# design.net
KiCad netlist of a schematic drawn in EasyEDA
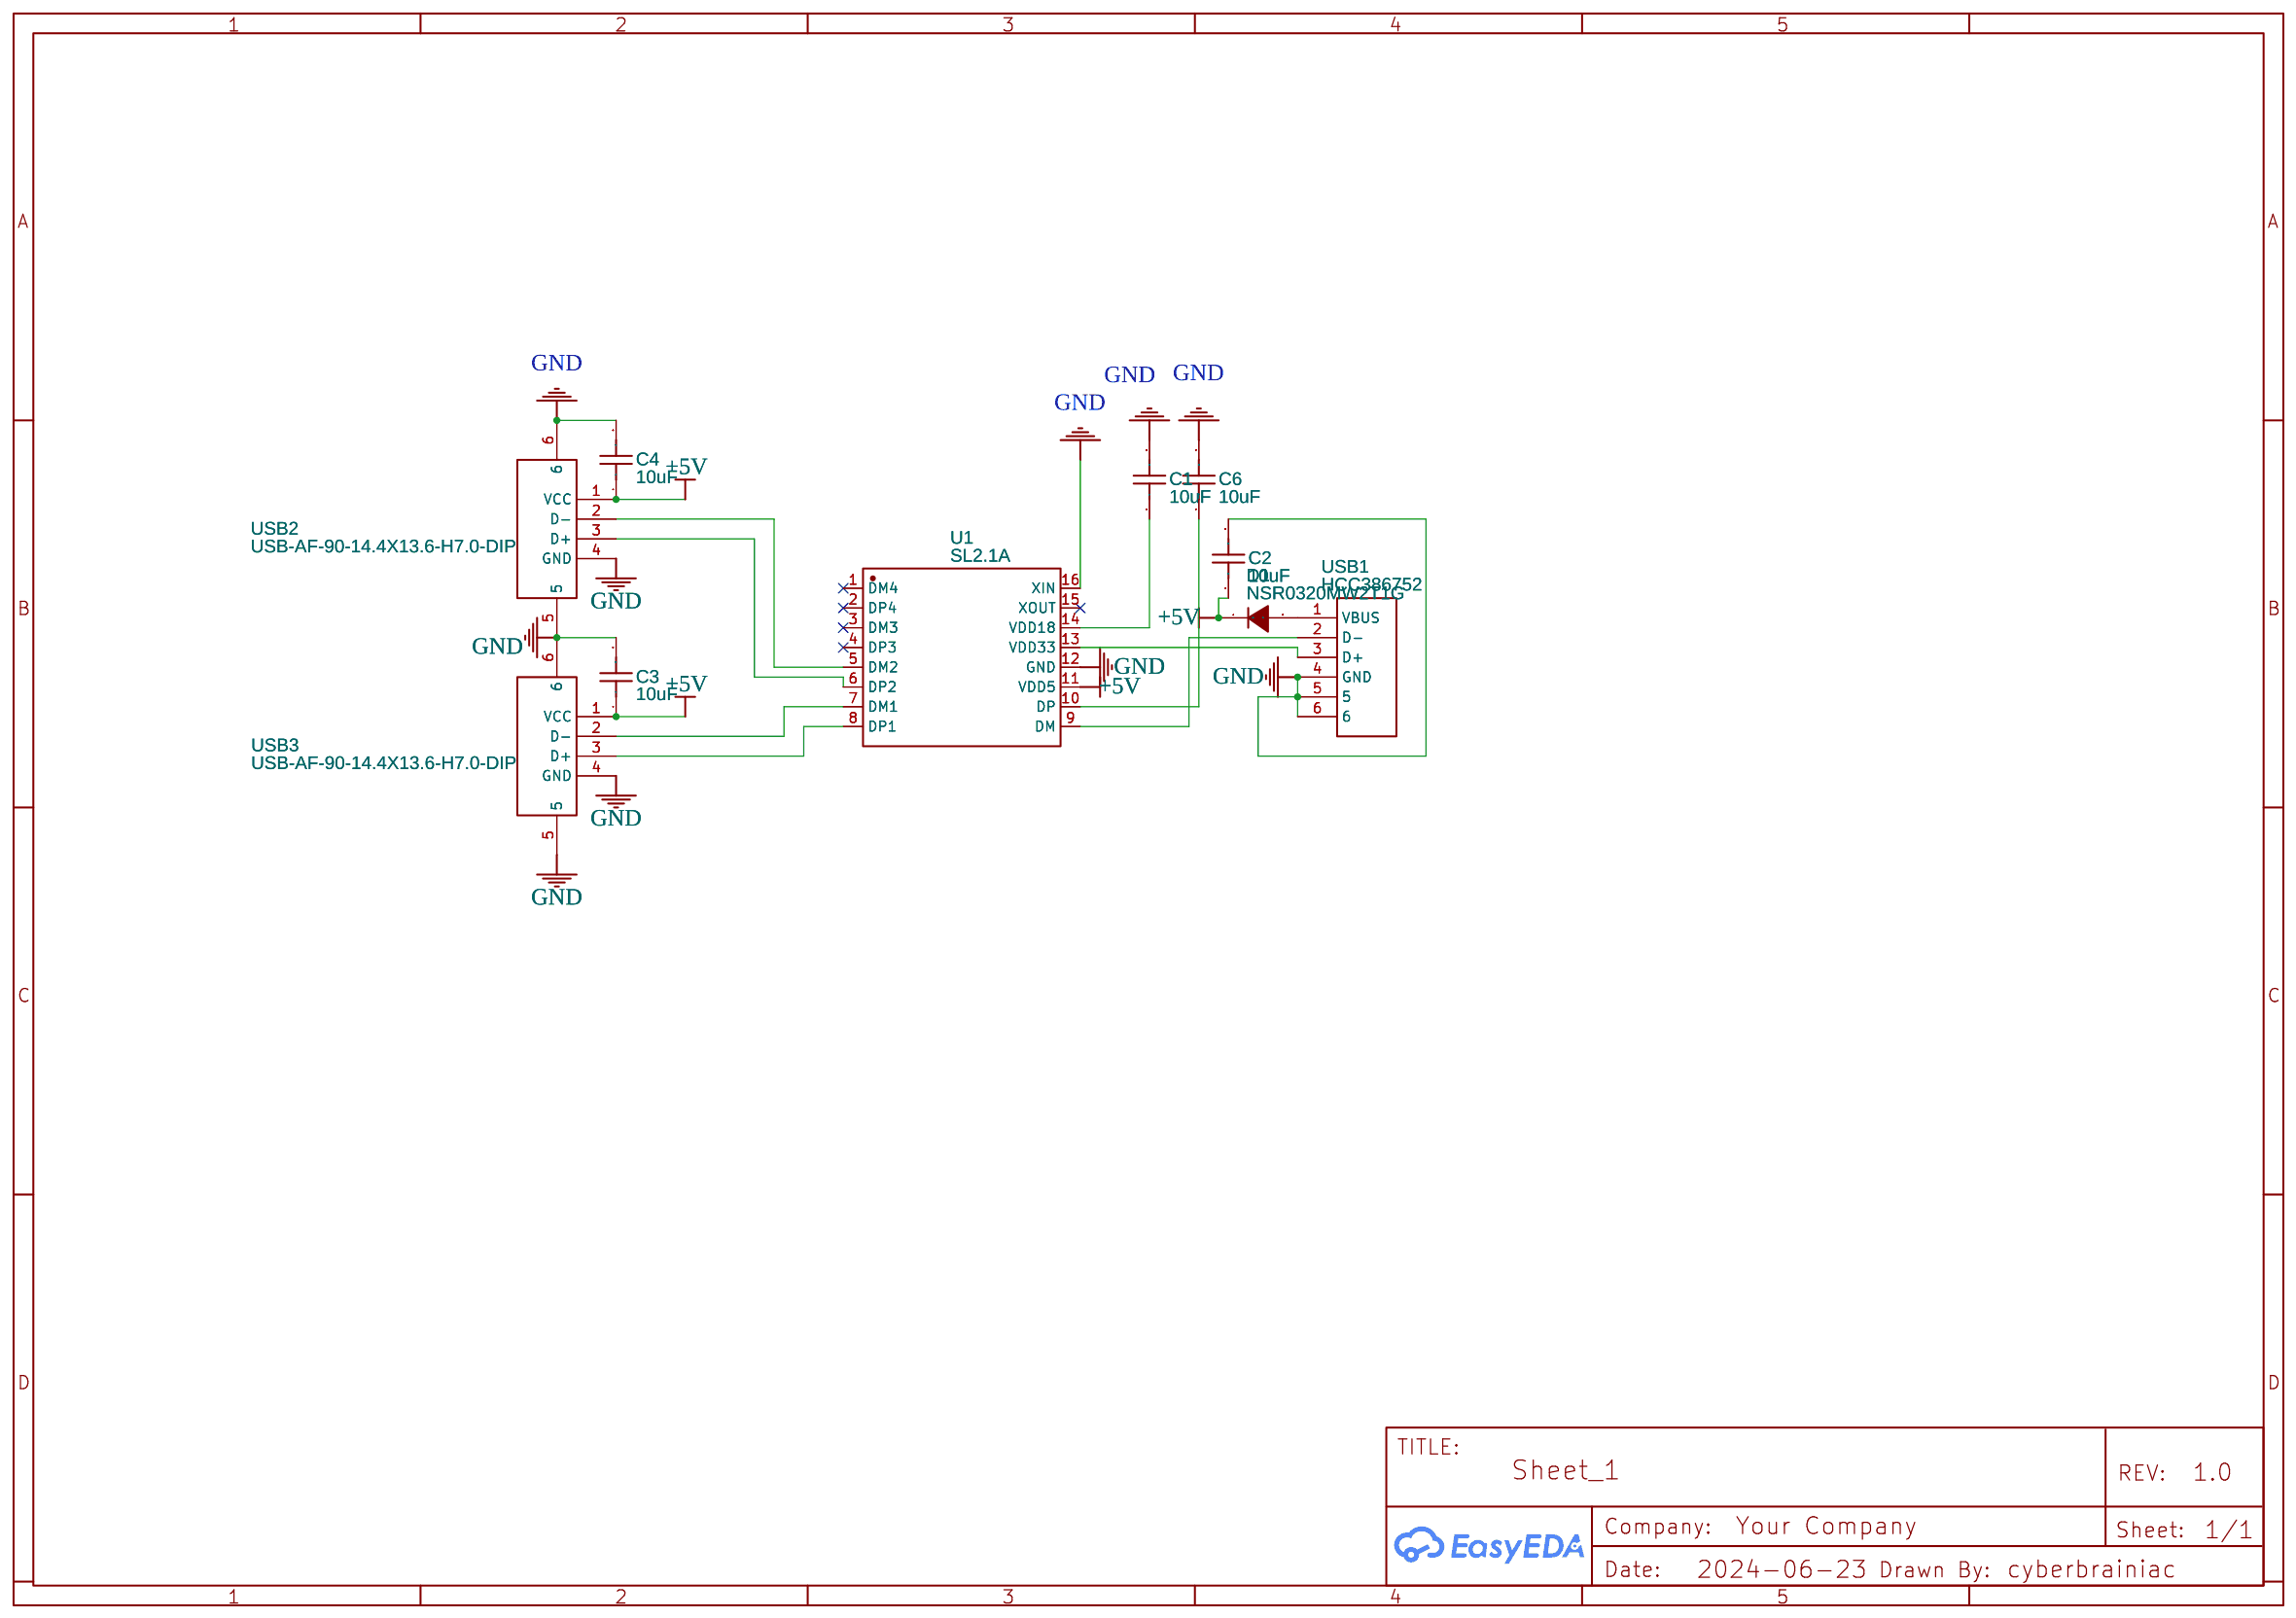
[diagram p0: schematic sheet]

(export (version "E")
  (design (tool "Eeschema 10.0.6"))
  (components
    (comp (ref "C1")
      (value "10uF")
      (fields
        (field (name "Manufacturer Part") "CL10A106KP8NNNC")
        (field (name "Manufacturer") "SAMSUNG(三星)")
      )
      (libsource (lib "") (part "CL10A106KP8NNNC"))
    )
    (comp (ref "C2")
      (value "10uF")
      (fields
        (field (name "Manufacturer Part") "CL10A106KP8NNNC")
        (field (name "Manufacturer") "SAMSUNG(三星)")
      )
      (libsource (lib "") (part "CL10A106KP8NNNC"))
    )
    (comp (ref "C3")
      (value "10uF")
      (fields
        (field (name "Manufacturer Part") "CL10A106KP8NNNC")
        (field (name "Manufacturer") "SAMSUNG(三星)")
      )
      (libsource (lib "") (part "CL10A106KP8NNNC"))
    )
    (comp (ref "C4")
      (value "10uF")
      (fields
        (field (name "Manufacturer Part") "CL10A106KP8NNNC")
        (field (name "Manufacturer") "SAMSUNG(三星)")
      )
      (libsource (lib "") (part "CL10A106KP8NNNC"))
    )
    (comp (ref "C6")
      (value "10uF")
      (fields
        (field (name "Manufacturer Part") "CL10A106KP8NNNC")
        (field (name "Manufacturer") "SAMSUNG(三星)")
      )
      (libsource (lib "") (part "CL10A106KP8NNNC"))
    )
    (comp (ref "D1")
      (value "NSR0320MW2T1G")
      (fields (field (name "Manufacturer") "onsemi(安森美)"))
      (libsource (lib "") (part "NSR0320MW2T1G"))
    )
    (comp (ref "U1")
      (value "SL2.1A")
      (fields (field (name "Manufacturer") "CoreChips(和芯润德)"))
      (libsource (lib "") (part "SL2.1A"))
    )
    (comp (ref "USB1")
      (value "HCC386752")
      (fields (field (name "Manufacturer Part") "U-USBAR04P-M003") (field (name "Manufacturer") "Ckmtw(灿科盟)"))
      (libsource (lib "") (part "HCC386752"))
    )
    (comp (ref "USB2")
      (value "USB-AF-90-14.4X13.6-H7.0-DIP")
      (fields (field (name "Manufacturer Part") "903-131A1011D10100") (field (name "Manufacturer") "精拓金"))
      (libsource (lib "") (part "USB-AF-90-14.4X13.6-H7.0-DIP"))
    )
    (comp (ref "USB3")
      (value "USB-AF-90-14.4X13.6-H7.0-DIP")
      (fields (field (name "Manufacturer Part") "903-131A1011D10100") (field (name "Manufacturer") "精拓金"))
      (libsource (lib "") (part "USB-AF-90-14.4X13.6-H7.0-DIP"))
    )
  )
  (nets
    (net (code "1") (name "+5V") (class "Default")
      (node (ref "C2") (pin "1") (pinfunction "1_1") (pintype "unspecified"))
      (node (ref "C3") (pin "1") (pinfunction "1_1") (pintype "unspecified"))
      (node (ref "C4") (pin "1") (pinfunction "1_1") (pintype "unspecified"))
      (node (ref "D1") (pin "1") (pinfunction "C_1") (pintype "unspecified"))
      (node (ref "U1") (pin "11") (pinfunction "VDD5_11") (pintype "unspecified"))
      (node (ref "USB2") (pin "1") (pinfunction "VCC_1") (pintype "unspecified"))
      (node (ref "USB3") (pin "1") (pinfunction "VCC_1") (pintype "unspecified"))
    )
    (net (code "2") (name "GND") (class "Default")
      (node (ref "C1") (pin "2") (pinfunction "2_2") (pintype "unspecified"))
      (node (ref "C2") (pin "2") (pinfunction "2_2") (pintype "unspecified"))
      (node (ref "C3") (pin "2") (pinfunction "2_2") (pintype "unspecified"))
      (node (ref "C4") (pin "2") (pinfunction "2_2") (pintype "unspecified"))
      (node (ref "C6") (pin "2") (pinfunction "2_2") (pintype "unspecified"))
      (node (ref "U1") (pin "12") (pinfunction "GND_12") (pintype "unspecified"))
      (node (ref "U1") (pin "16") (pinfunction "XIN_16") (pintype "unspecified"))
      (node (ref "USB1") (pin "4") (pinfunction "GND_4") (pintype "unspecified"))
      (node (ref "USB1") (pin "5") (pinfunction "5_5") (pintype "unspecified"))
      (node (ref "USB1") (pin "6") (pinfunction "6_6") (pintype "unspecified"))
      (node (ref "USB2") (pin "4") (pinfunction "GND_4") (pintype "unspecified"))
      (node (ref "USB2") (pin "5") (pinfunction "5_5") (pintype "unspecified"))
      (node (ref "USB2") (pin "6") (pinfunction "6_6") (pintype "unspecified"))
      (node (ref "USB3") (pin "4") (pinfunction "GND_4") (pintype "unspecified"))
      (node (ref "USB3") (pin "5") (pinfunction "5_5") (pintype "unspecified"))
      (node (ref "USB3") (pin "6") (pinfunction "6_6") (pintype "unspecified"))
    )
    (net (code "3") (name "Net-(D1-A)") (class "Default")
      (node (ref "D1") (pin "2") (pinfunction "A_2") (pintype "unspecified"))
      (node (ref "USB1") (pin "1") (pinfunction "VBUS_1") (pintype "unspecified"))
    )
    (net (code "4") (name "Net-(U1-DM)") (class "Default")
      (node (ref "U1") (pin "9") (pinfunction "DM_9") (pintype "unspecified"))
      (node (ref "USB1") (pin "2") (pinfunction "D-_2") (pintype "unspecified"))
    )
    (net (code "5") (name "Net-(U1-DM1)") (class "Default")
      (node (ref "U1") (pin "7") (pinfunction "DM1_7") (pintype "unspecified"))
      (node (ref "USB3") (pin "2") (pinfunction "D-_2") (pintype "unspecified"))
    )
    (net (code "6") (name "Net-(U1-DM2)") (class "Default")
      (node (ref "U1") (pin "5") (pinfunction "DM2_5") (pintype "unspecified"))
      (node (ref "USB2") (pin "2") (pinfunction "D-_2") (pintype "unspecified"))
    )
    (net (code "7") (name "Net-(U1-DP)") (class "Default")
      (node (ref "C6") (pin "1") (pinfunction "1_1") (pintype "unspecified"))
      (node (ref "U1") (pin "10") (pinfunction "DP_10") (pintype "unspecified"))
      (node (ref "U1") (pin "13") (pinfunction "VDD33_13") (pintype "unspecified"))
      (node (ref "USB1") (pin "3") (pinfunction "D+_3") (pintype "unspecified"))
    )
    (net (code "8") (name "Net-(U1-DP1)") (class "Default")
      (node (ref "U1") (pin "8") (pinfunction "DP1_8") (pintype "unspecified"))
      (node (ref "USB3") (pin "3") (pinfunction "D+_3") (pintype "unspecified"))
    )
    (net (code "9") (name "Net-(U1-DP2)") (class "Default")
      (node (ref "U1") (pin "6") (pinfunction "DP2_6") (pintype "unspecified"))
      (node (ref "USB2") (pin "3") (pinfunction "D+_3") (pintype "unspecified"))
    )
    (net (code "10") (name "Net-(U1-VDD18)") (class "Default")
      (node (ref "C1") (pin "1") (pinfunction "1_1") (pintype "unspecified"))
      (node (ref "U1") (pin "14") (pinfunction "VDD18_14") (pintype "unspecified"))
    )
    (net (code "11") (name "unconnected-(U1-DM3-Pad3)") (class "Default")
      (node (ref "U1") (pin "3") (pinfunction "DM3_3") (pintype "unspecified+no_connect"))
    )
    (net (code "12") (name "unconnected-(U1-DM4-Pad1)") (class "Default")
      (node (ref "U1") (pin "1") (pinfunction "DM4_1") (pintype "unspecified+no_connect"))
    )
    (net (code "13") (name "unconnected-(U1-DP3-Pad4)") (class "Default")
      (node (ref "U1") (pin "4") (pinfunction "DP3_4") (pintype "unspecified+no_connect"))
    )
    (net (code "14") (name "unconnected-(U1-DP4-Pad2)") (class "Default")
      (node (ref "U1") (pin "2") (pinfunction "DP4_2") (pintype "unspecified+no_connect"))
    )
    (net (code "15") (name "unconnected-(U1-XOUT-Pad15)") (class "Default")
      (node (ref "U1") (pin "15") (pinfunction "XOUT_15") (pintype "unspecified+no_connect"))
    )
  )
)
